# mapleCUx_large_340b-007.net
KiCad netlist of a schematic drawn in EAGLE
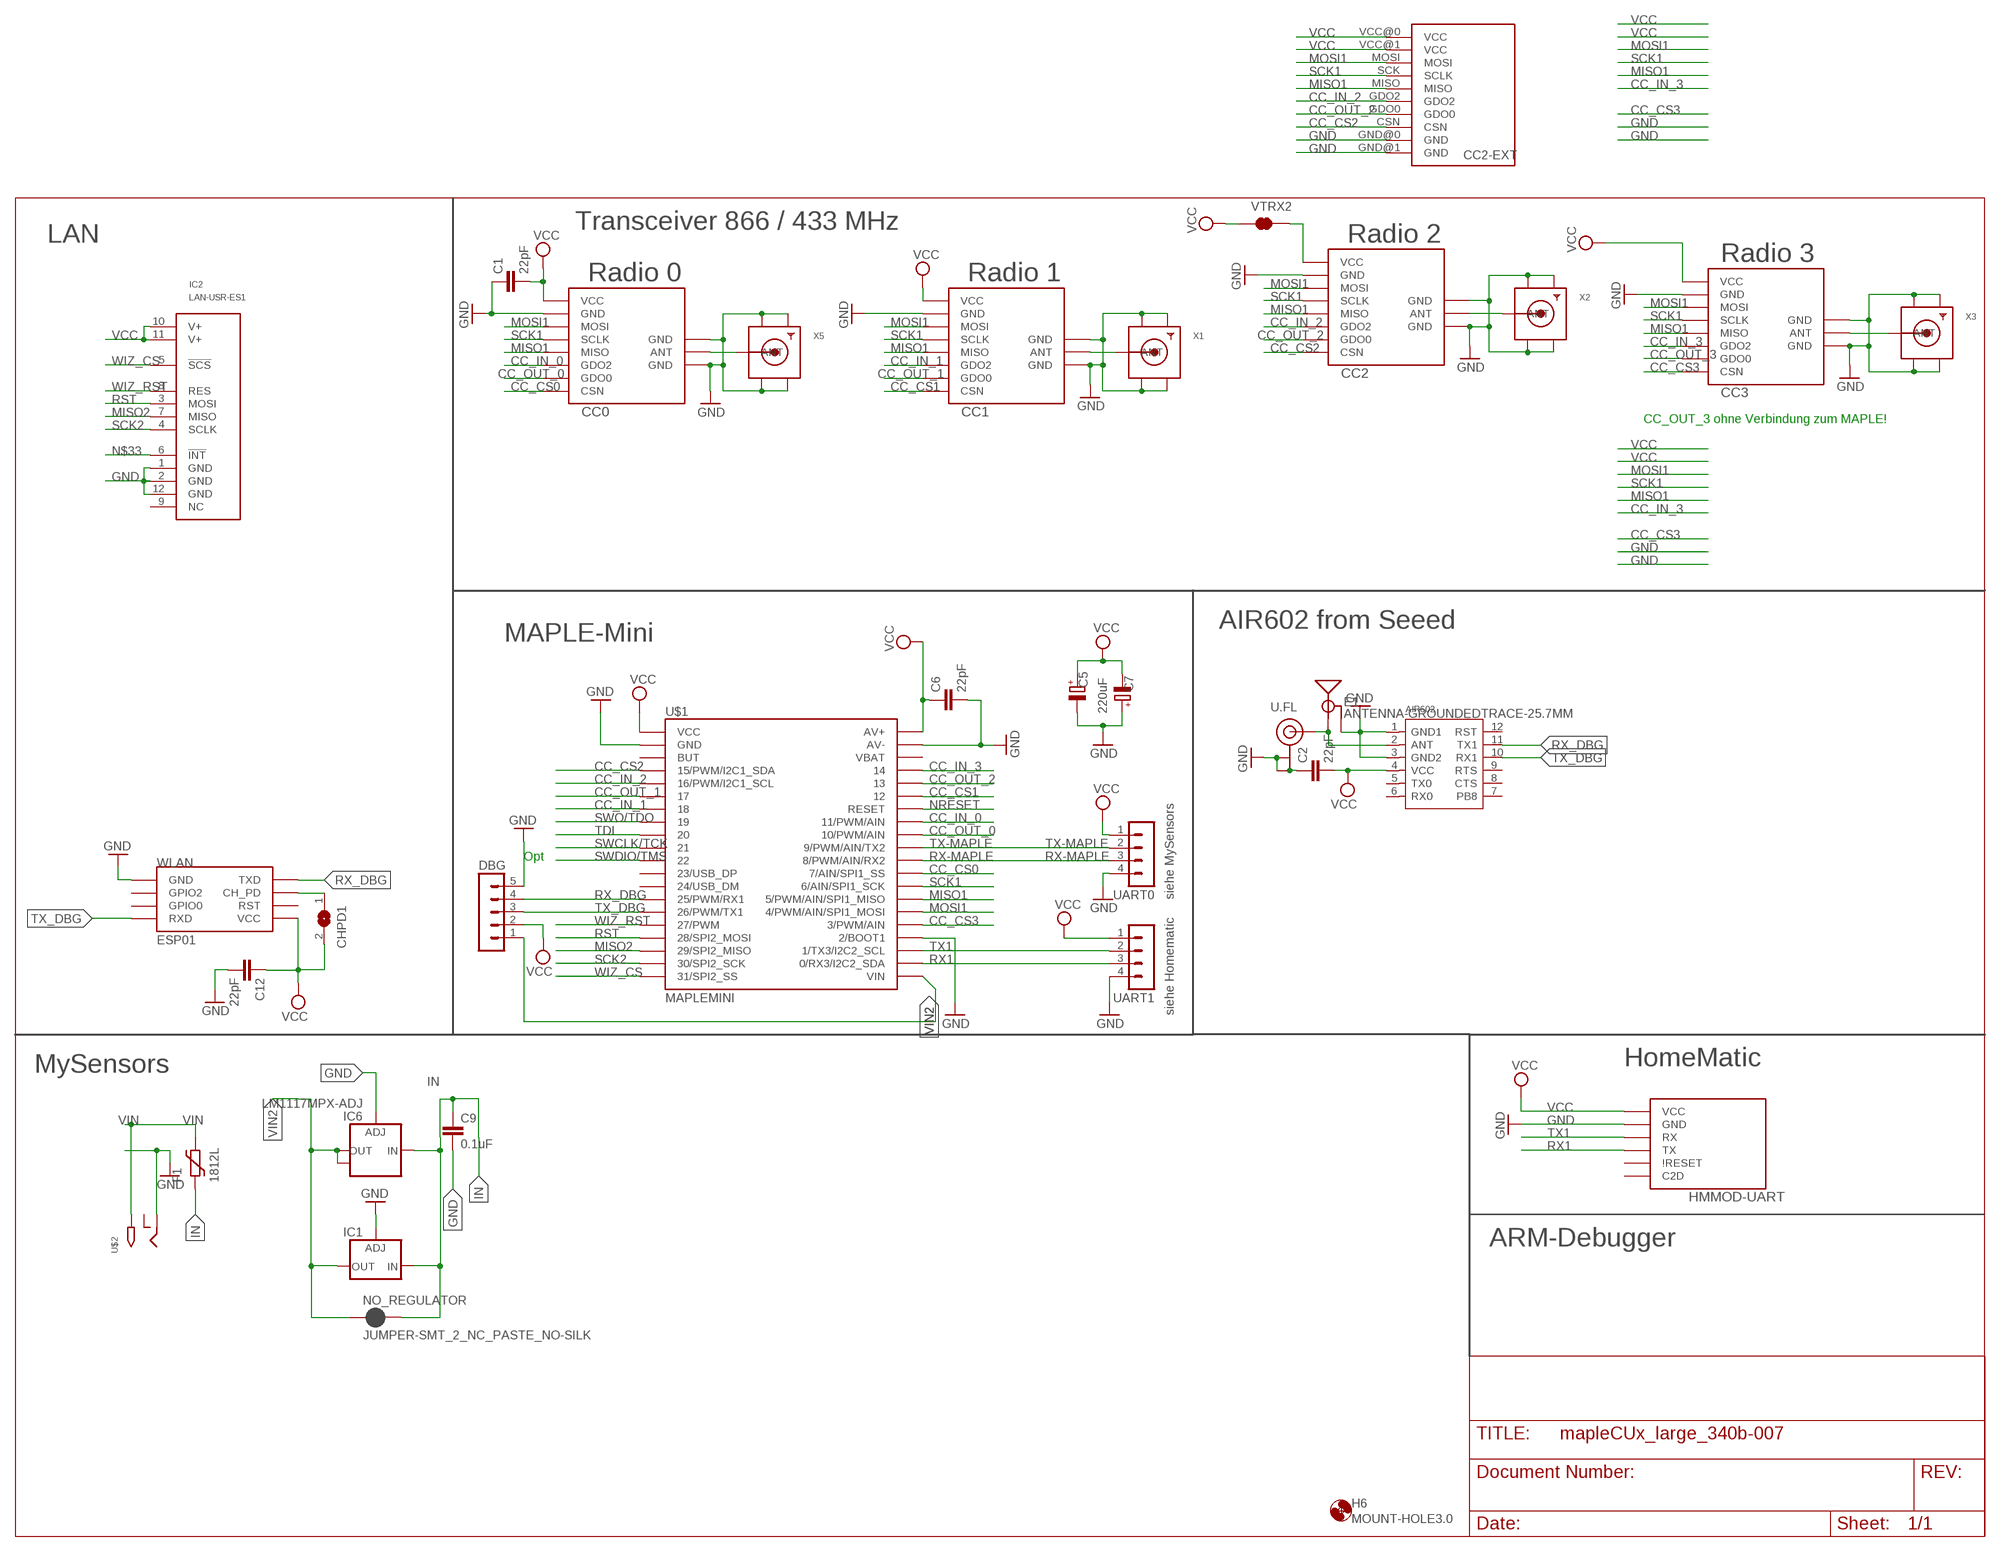
[diagram p0: schematic, sheet 1]

(export (version "E")
  (design (tool "Eeschema 10.0.6"))
  (components
    (comp (ref "AIR602")
      (value "AIR602")
      (footprint "eagle-import:MODULE12P-2.0-10X12MM")
      (libsource (lib "eagle-import") (part "AIR602"))
    )
    (comp (ref "C1")
      (value "22pF")
      (footprint "eagle-import:C0805")
      (libsource (lib "eagle-import") (part "C-EUC0805"))
    )
    (comp (ref "C2")
      (value "22pF")
      (footprint "eagle-import:C0805")
      (libsource (lib "eagle-import") (part "C-EUC0805"))
    )
    (comp (ref "C5")
      (value "220uF")
      (footprint "eagle-import:E5-8,5")
      (libsource (lib "eagle-import") (part "CPOL-EUE5-8.5"))
    )
    (comp (ref "C6")
      (value "22pF")
      (footprint "eagle-import:C0805")
      (libsource (lib "eagle-import") (part "C-EUC0805"))
    )
    (comp (ref "C7")
      (value "CPOL-EUSMCE")
      (footprint "eagle-import:SMC_E")
      (libsource (lib "eagle-import") (part "rcl_334_CPOL-EUSMCE"))
    )
    (comp (ref "C9")
      (value "0.1uF")
      (footprint "eagle-import:C1206")
      (libsource (lib "eagle-import") (part "C-EUC1206"))
    )
    (comp (ref "C12")
      (value "22pF")
      (footprint "eagle-import:C0805")
      (libsource (lib "eagle-import") (part "C-EUC0805"))
    )
    (comp (ref "CC0")
      (value "CC1101")
      (footprint "eagle-import:CC1101_MODULE1_SMD")
      (libsource (lib "eagle-import") (part "CC1101_MODULE1SMD"))
    )
    (comp (ref "CC1")
      (value "CC1101_MODULE1SMD")
      (footprint "eagle-import:CC1101_MODULE1_SMD")
      (libsource (lib "eagle-import") (part "CC1101_MODULE1SMD"))
    )
    (comp (ref "CC2")
      (value "CC1101_MODULE1SMD")
      (footprint "eagle-import:CC1101_MODULE1_SMD")
      (libsource (lib "eagle-import") (part "CC1101_MODULE1SMD"))
    )
    (comp (ref "CC2-EXT")
      (value "CC1101_MODULE3_DIL")
      (footprint "eagle-import:CC1101_MODULE3_DIL")
      (libsource (lib "eagle-import") (part "CC1101_MODULE3_DIL"))
    )
    (comp (ref "CC3")
      (value "CC1101_MODULE1SMD")
      (footprint "eagle-import:CC1101_MODULE1_SMD")
      (libsource (lib "eagle-import") (part "CC1101_MODULE1SMD"))
    )
    (comp (ref "CHPD1")
      (value "SJ")
      (footprint "eagle-import:SJ")
      (libsource (lib "eagle-import") (part "SJ"))
    )
    (comp (ref "DBG")
      (value "MA05-1")
      (footprint "eagle-import:MA05-1")
      (libsource (lib "eagle-import") (part "MA05-1"))
    )
    (comp (ref "E1")
      (value "ANTENNA-GROUNDEDTRACE-25.7MM")
      (footprint "eagle-import:TRACE_ANTENNA_2.4GHZ_25.7MM")
      (libsource (lib "eagle-import") (part "ANTENNA-GROUNDEDTRACE-25.7MM"))
    )
    (comp (ref "F1")
      (value "1812L")
      (footprint "eagle-import:1812L")
      (libsource (lib "eagle-import") (part "1812L"))
    )
    (comp (ref "H6")
      (value "MOUNT-HOLE3.0")
      (footprint "eagle-import:3,0")
      (libsource (lib "eagle-import") (part "MOUNT-HOLE3.0"))
    )
    (comp (ref "HMMOD-UART")
      (value "HM-MOD-UARTDIL")
      (footprint "eagle-import:HM-MOD-UART-DIL")
      (libsource (lib "eagle-import") (part "HM-MOD-UARTDIL"))
    )
    (comp (ref "IC1")
      (value "LD117ADT50TR")
      (footprint "eagle-import:DPACK")
      (libsource (lib "eagle-import") (part "LD117A?DT50TR"))
    )
    (comp (ref "IC2")
      (value "LAN-USR-ES1")
      (footprint "eagle-import:USR-ES1")
      (libsource (lib "eagle-import") (part "LAN-USR-ES1"))
    )
    (comp (ref "IC6")
      (value "LM1117MPX-ADJ")
      (footprint "eagle-import:SOT223")
      (libsource (lib "eagle-import") (part "LM1117MPX-ADJ"))
    )
    (comp (ref "NO_REGULATOR")
      (value "JUMPER-SMT_2_NC_PASTE_NO-SILK")
      (footprint "eagle-import:SMT-JUMPER_2_NC_PASTE_NO-SILK")
      (libsource (lib "eagle-import") (part "JUMPER-SMT_2_NC_PASTE_NO-SILK"))
    )
    (comp (ref "U$1")
      (value "MAPLEMINI")
      (footprint "eagle-import:20-DIP")
      (libsource (lib "eagle-import") (part "MAPLEMINI"))
    )
    (comp (ref "U$2")
      (value "2.1MMJACKTHM")
      (footprint "eagle-import:PJ-102A")
      (libsource (lib "eagle-import") (part "2.1MMJACKTHM"))
    )
    (comp (ref "U.FL")
      (value "U.FL")
      (footprint "eagle-import:U.FL")
      (libsource (lib "eagle-import") (part "U.FL"))
    )
    (comp (ref "UART0")
      (value "MA04-1")
      (footprint "eagle-import:MA04-1")
      (libsource (lib "eagle-import") (part "MA04-1"))
    )
    (comp (ref "UART1")
      (value "MA04-1")
      (footprint "eagle-import:MA04-1")
      (libsource (lib "eagle-import") (part "MA04-1"))
    )
    (comp (ref "VTRX2")
      (value "JUMPER-SMT_2_NC_TRACE_SILK")
      (footprint "eagle-import:SMT-JUMPER_2_NC_TRACE_SILK")
      (libsource (lib "eagle-import") (part "JUMPER-SMT_2_NC_TRACE_SILK"))
    )
    (comp (ref "WLAN")
      (value "ESP01")
      (footprint "eagle-import:ESP01")
      (libsource (lib "eagle-import") (part "ESP01"))
    )
    (comp (ref "X1")
      (value "SMACONNECTOR_EDGE")
      (footprint "eagle-import:SMA_EDGELAUNCH")
      (libsource (lib "eagle-import") (part "SMACONNECTOR_EDGE"))
    )
    (comp (ref "X2")
      (value "SMACONNECTOR_EDGE")
      (footprint "eagle-import:SMA_EDGELAUNCH")
      (libsource (lib "eagle-import") (part "SMACONNECTOR_EDGE"))
    )
    (comp (ref "X3")
      (value "SMACONNECTOR_EDGE")
      (footprint "eagle-import:SMA_EDGELAUNCH")
      (libsource (lib "eagle-import") (part "SMACONNECTOR_EDGE"))
    )
    (comp (ref "X5")
      (value "SMACONNECTOR_EDGE")
      (footprint "eagle-import:SMA_EDGELAUNCH")
      (libsource (lib "eagle-import") (part "SMACONNECTOR_EDGE"))
    )
  )
  (nets
    (net (code "1") (name "/CC_CS0") (class "Default")
      (node (ref "CC0") (pin "CSN") (pinfunction "CSN_CSN") (pintype "bidirectional"))
      (node (ref "U$1") (pin "29") (pinfunction "7/AIN/SPI1_SS_29") (pintype "bidirectional"))
    )
    (net (code "2") (name "/CC_CS1") (class "Default")
      (node (ref "CC1") (pin "CSN") (pinfunction "CSN_CSN") (pintype "bidirectional"))
      (node (ref "U$1") (pin "35") (pinfunction "12_35") (pintype "bidirectional"))
    )
    (net (code "3") (name "/CC_CS2") (class "Default")
      (node (ref "CC2") (pin "CSN") (pinfunction "CSN_CSN") (pintype "bidirectional"))
      (node (ref "CC2-EXT") (pin "CSN") (pinfunction "CSN_CSN") (pintype "bidirectional"))
      (node (ref "U$1") (pin "4") (pinfunction "15/PWM/I2C1_SDA_4") (pintype "bidirectional"))
    )
    (net (code "4") (name "/CC_CS3") (class "Default")
      (node (ref "CC3") (pin "CSN") (pinfunction "CSN_CSN") (pintype "bidirectional"))
      (node (ref "U$1") (pin "25") (pinfunction "3/PWM/AIN_25") (pintype "bidirectional"))
    )
    (net (code "5") (name "/CC_IN_0") (class "Default")
      (node (ref "CC0") (pin "GDO2") (pinfunction "GDO2_GDO2") (pintype "bidirectional"))
      (node (ref "U$1") (pin "33") (pinfunction "11/PWM/AIN_33") (pintype "bidirectional"))
    )
    (net (code "6") (name "/CC_IN_1") (class "Default")
      (node (ref "CC1") (pin "GDO2") (pinfunction "GDO2_GDO2") (pintype "bidirectional"))
      (node (ref "U$1") (pin "7") (pinfunction "18_7") (pintype "bidirectional"))
    )
    (net (code "7") (name "/CC_IN_2") (class "Default")
      (node (ref "CC2") (pin "GDO2") (pinfunction "GDO2_GDO2") (pintype "bidirectional"))
      (node (ref "CC2-EXT") (pin "GDO2") (pinfunction "GDO2_GDO2") (pintype "bidirectional"))
      (node (ref "U$1") (pin "5") (pinfunction "16/PWM/I2C1_SCL_5") (pintype "bidirectional"))
    )
    (net (code "8") (name "/CC_IN_3") (class "Default")
      (node (ref "CC3") (pin "GDO2") (pinfunction "GDO2_GDO2") (pintype "bidirectional"))
      (node (ref "U$1") (pin "37") (pinfunction "14_37") (pintype "bidirectional"))
    )
    (net (code "9") (name "/CC_OUT_0") (class "Default")
      (node (ref "CC0") (pin "GDO0") (pinfunction "GDO0_GDO0") (pintype "bidirectional"))
      (node (ref "U$1") (pin "32") (pinfunction "10/PWM/AIN_32") (pintype "bidirectional"))
    )
    (net (code "10") (name "/CC_OUT_1") (class "Default")
      (node (ref "CC1") (pin "GDO0") (pinfunction "GDO0_GDO0") (pintype "bidirectional"))
      (node (ref "U$1") (pin "6") (pinfunction "17_6") (pintype "bidirectional"))
    )
    (net (code "11") (name "/CC_OUT_2") (class "Default")
      (node (ref "CC2") (pin "GDO0") (pinfunction "GDO0_GDO0") (pintype "bidirectional"))
      (node (ref "CC2-EXT") (pin "GDO0") (pinfunction "GDO0_GDO0") (pintype "bidirectional"))
      (node (ref "U$1") (pin "36") (pinfunction "13_36") (pintype "bidirectional"))
    )
    (net (code "12") (name "/CC_OUT_3") (class "Default")
      (node (ref "CC3") (pin "GDO0") (pinfunction "GDO0_GDO0") (pintype "bidirectional"))
    )
    (net (code "13") (name "/MISO1") (class "Default")
      (node (ref "CC0") (pin "MISO") (pinfunction "MISO_MISO") (pintype "bidirectional"))
      (node (ref "CC1") (pin "MISO") (pinfunction "MISO_MISO") (pintype "bidirectional"))
      (node (ref "CC2") (pin "MISO") (pinfunction "MISO_MISO") (pintype "bidirectional"))
      (node (ref "CC2-EXT") (pin "MISO") (pinfunction "MISO_MISO") (pintype "bidirectional"))
      (node (ref "CC3") (pin "MISO") (pinfunction "MISO_MISO") (pintype "bidirectional"))
      (node (ref "U$1") (pin "27") (pinfunction "5/PWM/AIN/SPI1_MISO_27") (pintype "bidirectional"))
    )
    (net (code "14") (name "/MISO2") (class "Default")
      (node (ref "IC2") (pin "7") (pinfunction "MISO_7") (pintype "bidirectional"))
      (node (ref "U$1") (pin "18") (pinfunction "29/SPI2_MISO_18") (pintype "bidirectional"))
    )
    (net (code "15") (name "/MOSI1") (class "Default")
      (node (ref "CC0") (pin "MOSI") (pinfunction "MOSI_MOSI") (pintype "bidirectional"))
      (node (ref "CC1") (pin "MOSI") (pinfunction "MOSI_MOSI") (pintype "bidirectional"))
      (node (ref "CC2") (pin "MOSI") (pinfunction "MOSI_MOSI") (pintype "bidirectional"))
      (node (ref "CC2-EXT") (pin "MOSI") (pinfunction "MOSI_MOSI") (pintype "bidirectional"))
      (node (ref "CC3") (pin "MOSI") (pinfunction "MOSI_MOSI") (pintype "bidirectional"))
      (node (ref "U$1") (pin "26") (pinfunction "4/PWM/AIN/SPI1_MOSI_26") (pintype "bidirectional"))
    )
    (net (code "16") (name "/N$33") (class "Default")
      (node (ref "IC2") (pin "6") (pinfunction "~{INT}_6") (pintype "output"))
    )
    (net (code "17") (name "/NRESET") (class "Default")
      (node (ref "U$1") (pin "34") (pinfunction "RESET_34") (pintype "bidirectional"))
    )
    (net (code "18") (name "/RST") (class "Default")
      (node (ref "IC2") (pin "3") (pinfunction "MOSI_3") (pintype "bidirectional"))
      (node (ref "U$1") (pin "17") (pinfunction "28/SPI2_MOSI_17") (pintype "bidirectional"))
    )
    (net (code "19") (name "/RX-MAPLE") (class "Default")
      (node (ref "U$1") (pin "30") (pinfunction "8/PWM/AIN/RX2_30") (pintype "bidirectional"))
      (node (ref "UART0") (pin "3") (pinfunction "3_3") (pintype "passive"))
    )
    (net (code "20") (name "/RX1") (class "Default")
      (node (ref "HMMOD-UART") (pin "5") (pinfunction "TX_5") (pintype "bidirectional"))
      (node (ref "U$1") (pin "22") (pinfunction "0/RX3/I2C2_SDA_22") (pintype "bidirectional"))
      (node (ref "UART1") (pin "3") (pinfunction "3_3") (pintype "passive"))
    )
    (net (code "21") (name "/SCK1") (class "Default")
      (node (ref "CC0") (pin "SCLK") (pinfunction "SCLK_SCLK") (pintype "bidirectional"))
      (node (ref "CC1") (pin "SCLK") (pinfunction "SCLK_SCLK") (pintype "bidirectional"))
      (node (ref "CC2") (pin "SCLK") (pinfunction "SCLK_SCLK") (pintype "bidirectional"))
      (node (ref "CC2-EXT") (pin "SCK") (pinfunction "SCLK_SCK") (pintype "bidirectional"))
      (node (ref "CC3") (pin "SCLK") (pinfunction "SCLK_SCLK") (pintype "bidirectional"))
      (node (ref "U$1") (pin "28") (pinfunction "6/AIN/SPI1_SCK_28") (pintype "bidirectional"))
    )
    (net (code "22") (name "/SCK2") (class "Default")
      (node (ref "IC2") (pin "4") (pinfunction "SCLK_4") (pintype "input"))
      (node (ref "U$1") (pin "19") (pinfunction "30/SPI2_SCK_19") (pintype "bidirectional"))
    )
    (net (code "23") (name "/SWCLK{slash}TCK") (class "Default")
      (node (ref "U$1") (pin "10") (pinfunction "21_10") (pintype "bidirectional"))
    )
    (net (code "24") (name "/SWDIO{slash}TMS") (class "Default")
      (node (ref "U$1") (pin "11") (pinfunction "22_11") (pintype "bidirectional"))
    )
    (net (code "25") (name "/SWO{slash}TDO") (class "Default")
      (node (ref "U$1") (pin "8") (pinfunction "19_8") (pintype "bidirectional"))
    )
    (net (code "26") (name "/TDI") (class "Default")
      (node (ref "U$1") (pin "9") (pinfunction "20_9") (pintype "bidirectional"))
    )
    (net (code "27") (name "/TX-MAPLE") (class "Default")
      (node (ref "U$1") (pin "31") (pinfunction "9/PWM/AIN/TX2_31") (pintype "bidirectional"))
      (node (ref "UART0") (pin "2") (pinfunction "2_2") (pintype "passive"))
    )
    (net (code "28") (name "/TX1") (class "Default")
      (node (ref "HMMOD-UART") (pin "6") (pinfunction "RX_6") (pintype "bidirectional"))
      (node (ref "U$1") (pin "23") (pinfunction "1/TX3/I2C2_SCL_23") (pintype "bidirectional"))
      (node (ref "UART1") (pin "2") (pinfunction "2_2") (pintype "passive"))
    )
    (net (code "29") (name "/VIN") (class "Default")
      (node (ref "F1") (pin "P$2") (pinfunction "2_P$2") (pintype "passive"))
      (node (ref "U$2") (pin "TIP") (pinfunction "TIP_TIP") (pintype "bidirectional"))
    )
    (net (code "30") (name "/WIZ_CS") (class "Default")
      (node (ref "IC2") (pin "5") (pinfunction "~{SCS}_5") (pintype "input"))
      (node (ref "U$1") (pin "20") (pinfunction "31/SPI2_SS_20") (pintype "bidirectional"))
    )
    (net (code "31") (name "/WIZ_RST") (class "Default")
      (node (ref "IC2") (pin "8") (pinfunction "RES_8") (pintype "input"))
      (node (ref "U$1") (pin "16") (pinfunction "27/PWM_16") (pintype "bidirectional"))
    )
    (net (code "32") (name "GND") (class "Default")
      (node (ref "AIR602") (pin "1") (pinfunction "GND1_1") (pintype "bidirectional"))
      (node (ref "AIR602") (pin "3") (pinfunction "GND2_3") (pintype "bidirectional"))
      (node (ref "C1") (pin "1") (pinfunction "1_1") (pintype "passive"))
      (node (ref "C12") (pin "2") (pinfunction "2_2") (pintype "passive"))
      (node (ref "C5") (pin "-") (pinfunction "-_-") (pintype "passive"))
      (node (ref "C6") (pin "2") (pinfunction "2_2") (pintype "passive"))
      (node (ref "C7") (pin "+") (pinfunction "+_+") (pintype "passive"))
      (node (ref "C9") (pin "2") (pinfunction "2_2") (pintype "passive"))
      (node (ref "CC0") (pin "GND@0") (pinfunction "GND_GND@0") (pintype "power_in"))
      (node (ref "CC0") (pin "GND@1") (pinfunction "GND_GND@1") (pintype "power_in"))
      (node (ref "CC0") (pin "GND@2") (pinfunction "GND_GND@2") (pintype "power_in"))
      (node (ref "CC1") (pin "GND@0") (pinfunction "GND_GND@0") (pintype "power_in"))
      (node (ref "CC1") (pin "GND@1") (pinfunction "GND_GND@1") (pintype "power_in"))
      (node (ref "CC1") (pin "GND@2") (pinfunction "GND_GND@2") (pintype "power_in"))
      (node (ref "CC2") (pin "GND@0") (pinfunction "GND_GND@0") (pintype "power_in"))
      (node (ref "CC2") (pin "GND@1") (pinfunction "GND_GND@1") (pintype "power_in"))
      (node (ref "CC2") (pin "GND@2") (pinfunction "GND_GND@2") (pintype "power_in"))
      (node (ref "CC2-EXT") (pin "GND@0") (pinfunction "GND_GND@0") (pintype "power_in"))
      (node (ref "CC2-EXT") (pin "GND@1") (pinfunction "GND_GND@1") (pintype "power_in"))
      (node (ref "CC3") (pin "GND@0") (pinfunction "GND_GND@0") (pintype "power_in"))
      (node (ref "CC3") (pin "GND@1") (pinfunction "GND_GND@1") (pintype "power_in"))
      (node (ref "CC3") (pin "GND@2") (pinfunction "GND_GND@2") (pintype "power_in"))
      (node (ref "DBG") (pin "5") (pinfunction "5_5") (pintype "passive"))
      (node (ref "E1") (pin "GND") (pinfunction "GND_GND") (pintype "bidirectional"))
      (node (ref "E1") (pin "GND2") (pinfunction "GND_GND2") (pintype "bidirectional"))
      (node (ref "HMMOD-UART") (pin "2") (pinfunction "GND_2") (pintype "power_in"))
      (node (ref "IC1") (pin "1") (pinfunction "ADJ_1") (pintype "input"))
      (node (ref "IC2") (pin "1") (pinfunction "GND_1") (pintype "power_in"))
      (node (ref "IC2") (pin "12") (pinfunction "GND_12") (pintype "power_in"))
      (node (ref "IC2") (pin "2") (pinfunction "GND_2") (pintype "power_in"))
      (node (ref "IC6") (pin "1") (pinfunction "ADJ_1") (pintype "input"))
      (node (ref "U$1") (pin "2") (pinfunction "GND_2") (pintype "bidirectional"))
      (node (ref "U$1") (pin "24") (pinfunction "2/BOOT1_24") (pintype "bidirectional"))
      (node (ref "U$1") (pin "39") (pinfunction "AV-_39") (pintype "bidirectional"))
      (node (ref "U$2") (pin "RING") (pinfunction "RING_RING") (pintype "bidirectional"))
      (node (ref "U.FL") (pin "1") (pinfunction "GND_1") (pintype "bidirectional"))
      (node (ref "U.FL") (pin "2") (pinfunction "GND_2") (pintype "bidirectional"))
      (node (ref "UART0") (pin "4") (pinfunction "4_4") (pintype "passive"))
      (node (ref "UART1") (pin "4") (pinfunction "4_4") (pintype "passive"))
      (node (ref "WLAN") (pin "GND") (pinfunction "GND_GND") (pintype "bidirectional"))
      (node (ref "X1") (pin "GND@1") (pinfunction "GND4_GND@1") (pintype "power_in"))
      (node (ref "X1") (pin "GND@2") (pinfunction "GND3_GND@2") (pintype "power_in"))
      (node (ref "X1") (pin "GND@3") (pinfunction "GND2_GND@3") (pintype "power_in"))
      (node (ref "X1") (pin "GND@4") (pinfunction "GND1_GND@4") (pintype "power_in"))
      (node (ref "X2") (pin "GND@1") (pinfunction "GND4_GND@1") (pintype "power_in"))
      (node (ref "X2") (pin "GND@2") (pinfunction "GND3_GND@2") (pintype "power_in"))
      (node (ref "X2") (pin "GND@3") (pinfunction "GND2_GND@3") (pintype "power_in"))
      (node (ref "X2") (pin "GND@4") (pinfunction "GND1_GND@4") (pintype "power_in"))
      (node (ref "X3") (pin "GND@1") (pinfunction "GND4_GND@1") (pintype "power_in"))
      (node (ref "X3") (pin "GND@2") (pinfunction "GND3_GND@2") (pintype "power_in"))
      (node (ref "X3") (pin "GND@3") (pinfunction "GND2_GND@3") (pintype "power_in"))
      (node (ref "X3") (pin "GND@4") (pinfunction "GND1_GND@4") (pintype "power_in"))
      (node (ref "X5") (pin "GND@1") (pinfunction "GND4_GND@1") (pintype "power_in"))
      (node (ref "X5") (pin "GND@2") (pinfunction "GND3_GND@2") (pintype "power_in"))
      (node (ref "X5") (pin "GND@3") (pinfunction "GND2_GND@3") (pintype "power_in"))
      (node (ref "X5") (pin "GND@4") (pinfunction "GND1_GND@4") (pintype "power_in"))
    )
    (net (code "33") (name "IN") (class "Default")
      (node (ref "C9") (pin "1") (pinfunction "1_1") (pintype "passive"))
      (node (ref "F1") (pin "P$1") (pinfunction "1_P$1") (pintype "passive"))
      (node (ref "IC1") (pin "3") (pinfunction "IN_3") (pintype "input"))
      (node (ref "IC6") (pin "3") (pinfunction "IN_3") (pintype "input"))
      (node (ref "NO_REGULATOR") (pin "2") (pinfunction "2_2") (pintype "passive"))
    )
    (net (code "34") (name "Net-(AIR602-ANT)") (class "Default")
      (node (ref "AIR602") (pin "2") (pinfunction "ANT_2") (pintype "bidirectional"))
      (node (ref "E1") (pin "ANT") (pinfunction "SIGNAL_ANT") (pintype "bidirectional"))
      (node (ref "U.FL") (pin "FEED") (pinfunction "SIGNAL_FEED") (pintype "bidirectional"))
    )
    (net (code "35") (name "Net-(CC2-PadVCC)") (class "Default")
      (node (ref "CC2") (pin "VCC") (pinfunction "VCC_VCC") (pintype "power_in"))
      (node (ref "VTRX2") (pin "2") (pinfunction "2_2") (pintype "passive"))
    )
    (net (code "36") (name "Net-(CHPD1-Pad1)") (class "Default")
      (node (ref "CHPD1") (pin "1") (pinfunction "1_1") (pintype "passive"))
      (node (ref "WLAN") (pin "CH_PD") (pinfunction "CH_PD_CH_PD") (pintype "bidirectional"))
    )
    (net (code "37") (name "Net-(X1-ANT)") (class "Default")
      (node (ref "CC1") (pin "ANT") (pinfunction "ANT_ANT") (pintype "output"))
      (node (ref "X1") (pin "P") (pinfunction "ANT_P") (pintype "bidirectional"))
    )
    (net (code "38") (name "Net-(X2-ANT)") (class "Default")
      (node (ref "CC2") (pin "ANT") (pinfunction "ANT_ANT") (pintype "output"))
      (node (ref "X2") (pin "P") (pinfunction "ANT_P") (pintype "bidirectional"))
    )
    (net (code "39") (name "Net-(X3-ANT)") (class "Default")
      (node (ref "CC3") (pin "ANT") (pinfunction "ANT_ANT") (pintype "output"))
      (node (ref "X3") (pin "P") (pinfunction "ANT_P") (pintype "bidirectional"))
    )
    (net (code "40") (name "Net-(X5-ANT)") (class "Default")
      (node (ref "CC0") (pin "ANT") (pinfunction "ANT_ANT") (pintype "output"))
      (node (ref "X5") (pin "P") (pinfunction "ANT_P") (pintype "bidirectional"))
    )
    (net (code "41") (name "RX_DBG") (class "Default")
      (node (ref "AIR602") (pin "11") (pinfunction "TX1_11") (pintype "bidirectional"))
      (node (ref "DBG") (pin "4") (pinfunction "4_4") (pintype "passive"))
      (node (ref "U$1") (pin "14") (pinfunction "25/PWM/RX1_14") (pintype "bidirectional"))
      (node (ref "WLAN") (pin "TX") (pinfunction "TXD_TX") (pintype "bidirectional"))
    )
    (net (code "42") (name "TX_DBG") (class "Default")
      (node (ref "AIR602") (pin "10") (pinfunction "RX1_10") (pintype "bidirectional"))
      (node (ref "DBG") (pin "3") (pinfunction "3_3") (pintype "passive"))
      (node (ref "U$1") (pin "15") (pinfunction "26/PWM/TX1_15") (pintype "bidirectional"))
      (node (ref "WLAN") (pin "RX") (pinfunction "RXD_RX") (pintype "bidirectional"))
    )
    (net (code "43") (name "VCC") (class "Default")
      (node (ref "AIR602") (pin "4") (pinfunction "VCC_4") (pintype "bidirectional"))
      (node (ref "C1") (pin "2") (pinfunction "2_2") (pintype "passive"))
      (node (ref "C12") (pin "1") (pinfunction "1_1") (pintype "passive"))
      (node (ref "C2") (pin "2") (pinfunction "2_2") (pintype "passive"))
      (node (ref "C5") (pin "+") (pinfunction "+_+") (pintype "passive"))
      (node (ref "C6") (pin "1") (pinfunction "1_1") (pintype "passive"))
      (node (ref "C7") (pin "-") (pinfunction "-_-") (pintype "passive"))
      (node (ref "CC0") (pin "VCC") (pinfunction "VCC_VCC") (pintype "power_in"))
      (node (ref "CC1") (pin "VCC") (pinfunction "VCC_VCC") (pintype "power_in"))
      (node (ref "CC2-EXT") (pin "VCC@0") (pinfunction "VCC_VCC@0") (pintype "power_in"))
      (node (ref "CC2-EXT") (pin "VCC@1") (pinfunction "VCC_VCC@1") (pintype "power_in"))
      (node (ref "CC3") (pin "VCC") (pinfunction "VCC_VCC") (pintype "power_in"))
      (node (ref "CHPD1") (pin "2") (pinfunction "2_2") (pintype "passive"))
      (node (ref "DBG") (pin "2") (pinfunction "2_2") (pintype "passive"))
      (node (ref "HMMOD-UART") (pin "1") (pinfunction "VCC_1") (pintype "power_in"))
      (node (ref "IC2") (pin "10") (pinfunction "V+_10") (pintype "power_in"))
      (node (ref "IC2") (pin "11") (pinfunction "V+_11") (pintype "power_in"))
      (node (ref "U$1") (pin "1") (pinfunction "VCC_1") (pintype "bidirectional"))
      (node (ref "U$1") (pin "40") (pinfunction "AV+_40") (pintype "bidirectional"))
      (node (ref "UART0") (pin "1") (pinfunction "1_1") (pintype "passive"))
      (node (ref "UART1") (pin "1") (pinfunction "1_1") (pintype "passive"))
      (node (ref "VTRX2") (pin "1") (pinfunction "1_1") (pintype "passive"))
      (node (ref "WLAN") (pin "VCC") (pinfunction "VCC_VCC") (pintype "bidirectional"))
    )
    (net (code "44") (name "VIN2") (class "Default")
      (node (ref "DBG") (pin "1") (pinfunction "1_1") (pintype "passive"))
      (node (ref "IC1") (pin "4") (pinfunction "OUT_4") (pintype "passive"))
      (node (ref "IC6") (pin "2") (pinfunction "OUT_2") (pintype "passive"))
      (node (ref "IC6") (pin "TAB") (pinfunction "OUT1_TAB") (pintype "passive"))
      (node (ref "NO_REGULATOR") (pin "1") (pinfunction "1_1") (pintype "passive"))
      (node (ref "U$1") (pin "21") (pinfunction "VIN_21") (pintype "bidirectional"))
    )
    (net (code "45") (name "unconnected-(AIR602-CTS-Pad8)") (class "Default")
      (node (ref "AIR602") (pin "8") (pinfunction "CTS_8") (pintype "bidirectional"))
    )
    (net (code "46") (name "unconnected-(AIR602-PB8-Pad7)") (class "Default")
      (node (ref "AIR602") (pin "7") (pinfunction "PB8_7") (pintype "bidirectional"))
    )
    (net (code "47") (name "unconnected-(AIR602-RST-Pad12)") (class "Default")
      (node (ref "AIR602") (pin "12") (pinfunction "RST_12") (pintype "bidirectional"))
    )
    (net (code "48") (name "unconnected-(AIR602-RTS-Pad9)") (class "Default")
      (node (ref "AIR602") (pin "9") (pinfunction "RTS_9") (pintype "bidirectional"))
    )
    (net (code "49") (name "unconnected-(AIR602-RX0-Pad6)") (class "Default")
      (node (ref "AIR602") (pin "6") (pinfunction "RX0_6") (pintype "bidirectional"))
    )
    (net (code "50") (name "unconnected-(AIR602-TX0-Pad5)") (class "Default")
      (node (ref "AIR602") (pin "5") (pinfunction "TX0_5") (pintype "bidirectional"))
    )
    (net (code "51") (name "unconnected-(C2-Pad1)") (class "Default")
      (node (ref "C2") (pin "1") (pinfunction "1_1") (pintype "passive"))
    )
    (net (code "52") (name "unconnected-(HMMOD-UART-C2D-Pad3)") (class "Default")
      (node (ref "HMMOD-UART") (pin "3") (pinfunction "C2D_3") (pintype "bidirectional"))
    )
    (net (code "53") (name "unconnected-(HMMOD-UART-\\~{RESET}-Pad4)") (class "Default")
      (node (ref "HMMOD-UART") (pin "4") (pinfunction "\\~{RESET}_4") (pintype "bidirectional"))
    )
    (net (code "54") (name "unconnected-(IC2-NC-Pad9)") (class "Default")
      (node (ref "IC2") (pin "9") (pinfunction "NC_9") (pintype "no_connect"))
    )
    (net (code "55") (name "unconnected-(U$1-23{slash}USB_DP-Pad12)") (class "Default")
      (node (ref "U$1") (pin "12") (pinfunction "23/USB_DP_12") (pintype "bidirectional"))
    )
    (net (code "56") (name "unconnected-(U$1-24{slash}USB_DM-Pad13)") (class "Default")
      (node (ref "U$1") (pin "13") (pinfunction "24/USB_DM_13") (pintype "bidirectional"))
    )
    (net (code "57") (name "unconnected-(U$1-BUT-Pad3)") (class "Default")
      (node (ref "U$1") (pin "3") (pinfunction "BUT_3") (pintype "bidirectional"))
    )
    (net (code "58") (name "unconnected-(U$1-VBAT-Pad38)") (class "Default")
      (node (ref "U$1") (pin "38") (pinfunction "VBAT_38") (pintype "bidirectional"))
    )
    (net (code "59") (name "unconnected-(U$2-PadRING_SW)") (class "Default")
      (node (ref "U$2") (pin "RING_SW") (pinfunction "RING_SW_RING_SW") (pintype "bidirectional"))
    )
    (net (code "60") (name "unconnected-(WLAN-PadGPIO0)") (class "Default")
      (node (ref "WLAN") (pin "GPIO0") (pinfunction "GPIO0_GPIO0") (pintype "bidirectional"))
    )
    (net (code "61") (name "unconnected-(WLAN-PadGPIO2)") (class "Default")
      (node (ref "WLAN") (pin "GPIO2") (pinfunction "GPIO2_GPIO2") (pintype "bidirectional"))
    )
    (net (code "62") (name "unconnected-(WLAN-PadRST)") (class "Default")
      (node (ref "WLAN") (pin "RST") (pinfunction "RST_RST") (pintype "bidirectional"))
    )
  )
)
